# sensorHubRev6.net
KiCad netlist of a schematic drawn in EAGLE
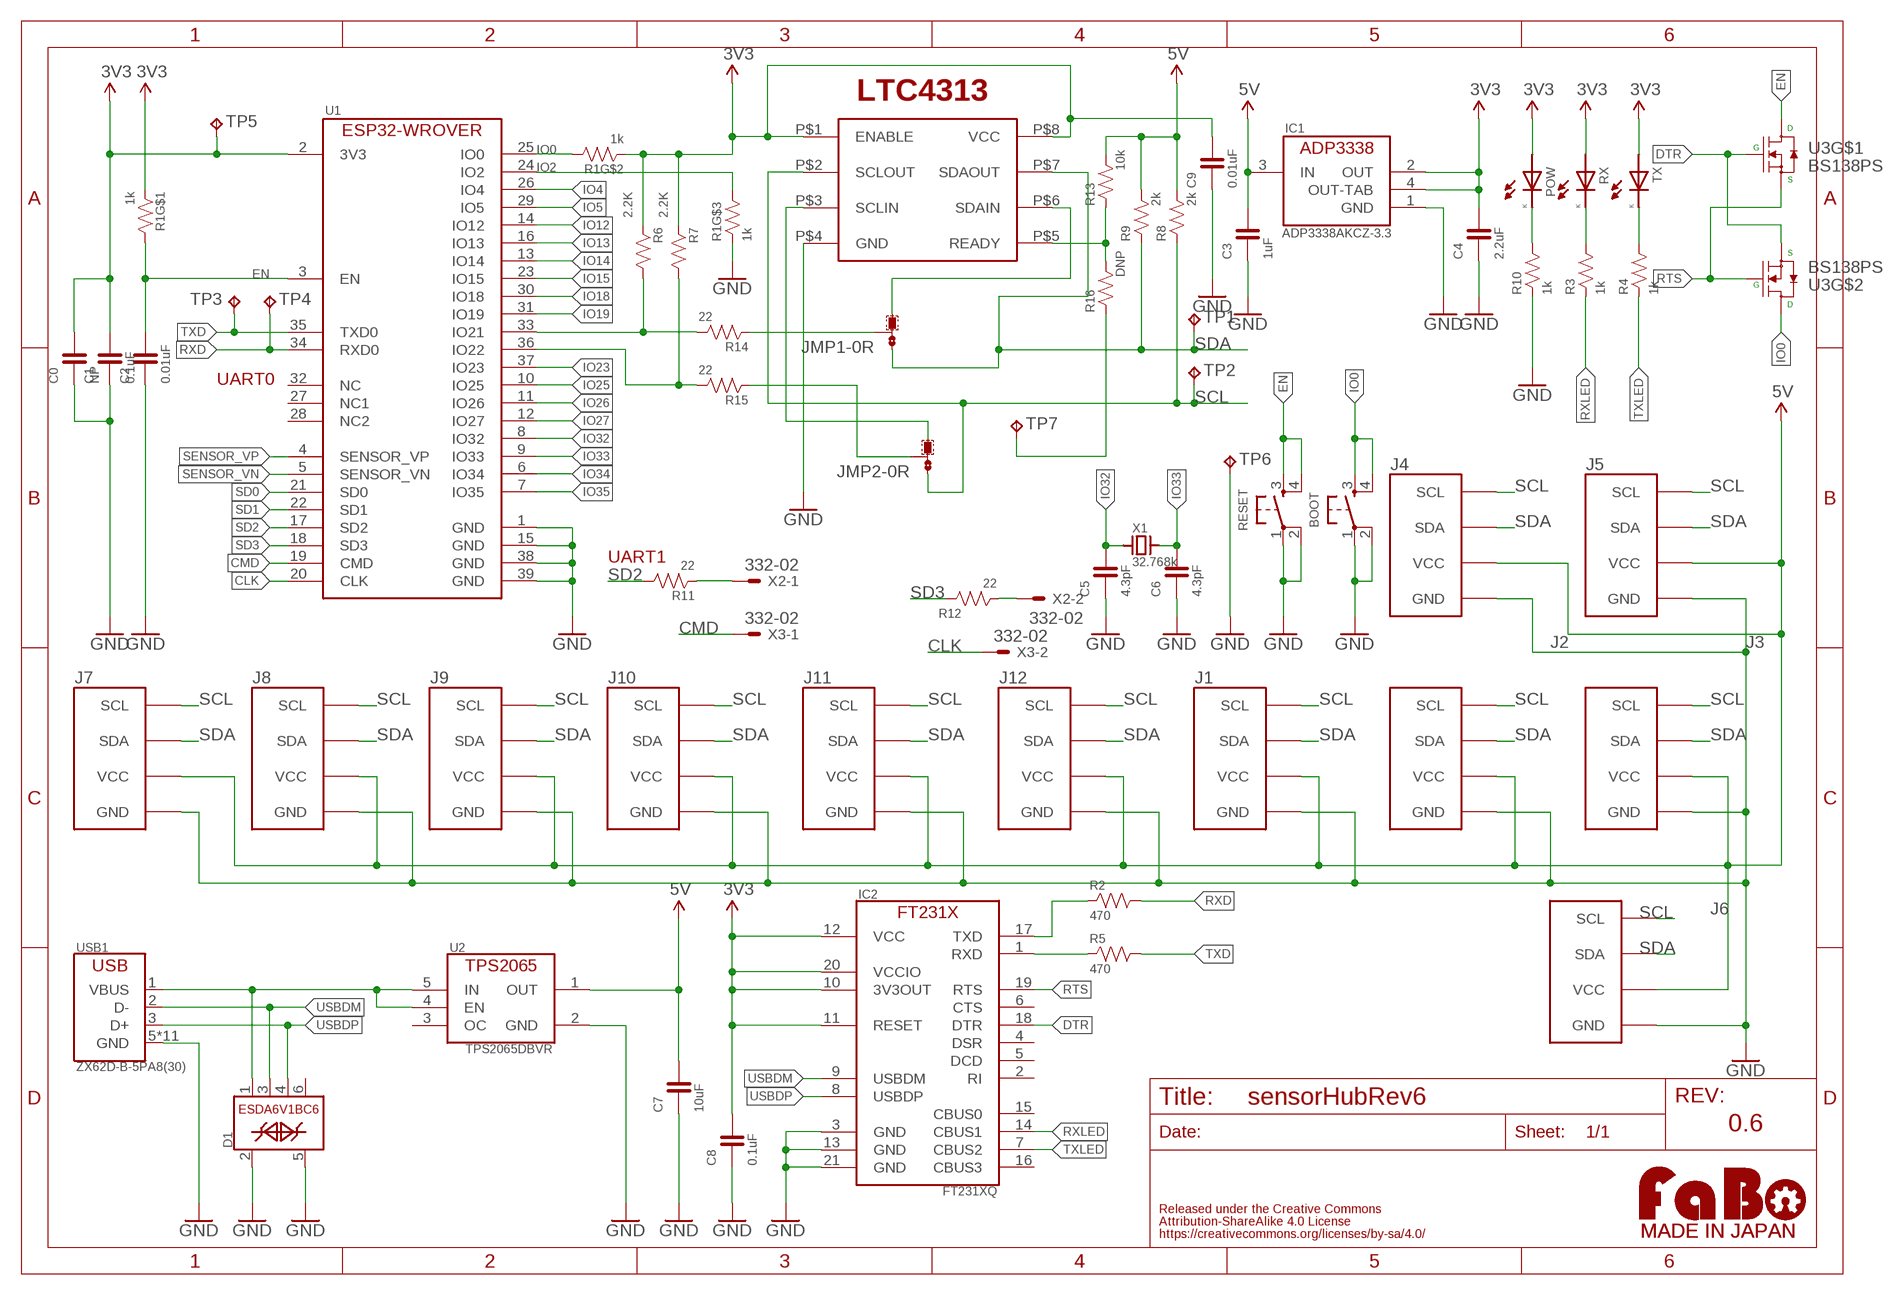
[diagram p0: schematic, sheet 1]

(export (version "E")
  (design (tool "Eeschema 10.0.6"))
  (components
    (comp (ref "BOOT")
      (value "TACTILE-KMR2")
      (footprint "eagle-import:KMR2-TACT")
      (libsource (lib "eagle-import") (part "TACTILE-KMR2"))
    )
    (comp (ref "C0")
      (value "NP")
      (footprint "eagle-import:MULTIPAD0603")
      (libsource (lib "eagle-import") (part "CAPACITOR-M"))
    )
    (comp (ref "C1")
      (value "0.1uF")
      (footprint "eagle-import:EIA0603")
      (libsource (lib "eagle-import") (part "CAPACITOR-0603"))
    )
    (comp (ref "C2")
      (value "0.01uF")
      (footprint "eagle-import:EIA0603")
      (libsource (lib "eagle-import") (part "CAPACITOR-0603"))
    )
    (comp (ref "C3")
      (value "1uF")
      (footprint "eagle-import:EIA0603")
      (libsource (lib "eagle-import") (part "CAPACITOR-0603"))
    )
    (comp (ref "C4")
      (value "2.2uF")
      (footprint "eagle-import:EIA0603")
      (libsource (lib "eagle-import") (part "CAPACITOR-0603"))
    )
    (comp (ref "C5")
      (value "4.3pF")
      (footprint "eagle-import:EIA0603")
      (libsource (lib "eagle-import") (part "CAPACITOR-0603"))
    )
    (comp (ref "C6")
      (value "4.3pF")
      (footprint "eagle-import:EIA0603")
      (libsource (lib "eagle-import") (part "CAPACITOR-0603"))
    )
    (comp (ref "C7")
      (value "10uF")
      (footprint "eagle-import:EIA0603")
      (libsource (lib "eagle-import") (part "CAPACITOR-0603"))
    )
    (comp (ref "C8")
      (value "0.1uF")
      (footprint "eagle-import:EIA0603")
      (libsource (lib "eagle-import") (part "CAPACITOR-0603"))
    )
    (comp (ref "C9")
      (value "0.01uF")
      (footprint "eagle-import:EIA0603")
      (libsource (lib "eagle-import") (part "CAPACITOR-0603"))
    )
    (comp (ref "D1")
      (value "ESDA6V1BC6")
      (footprint "eagle-import:SOT-23-6L")
      (libsource (lib "eagle-import") (part "ESDA6V1BC6"))
    )
    (comp (ref "IC1")
      (value "ADP3338AKCZ-3.3")
      (footprint "eagle-import:SOT-223-KC3")
      (libsource (lib "eagle-import") (part "ADP3338AKCZ"))
    )
    (comp (ref "IC2")
      (value "FT231XQ")
      (footprint "eagle-import:QFN-20")
      (libsource (lib "eagle-import") (part "FT231XQ"))
    )
    (comp (ref "J1")
      (value "FABO_BRICK_I2C-S04B-PASK-2")
      (footprint "eagle-import:FABO_BRICK_I2C_S04B-PASK-2")
      (libsource (lib "eagle-import") (part "FABO_BRICK_I2C-S04B-PASK-2"))
    )
    (comp (ref "J2")
      (value "FABO_BRICK_I2C-S04B-PASK-2")
      (footprint "eagle-import:FABO_BRICK_I2C_S04B-PASK-2")
      (libsource (lib "eagle-import") (part "FABO_BRICK_I2C-S04B-PASK-2"))
    )
    (comp (ref "J3")
      (value "FABO_BRICK_I2C-S04B-PASK-2")
      (footprint "eagle-import:FABO_BRICK_I2C_S04B-PASK-2")
      (libsource (lib "eagle-import") (part "FABO_BRICK_I2C-S04B-PASK-2"))
    )
    (comp (ref "J4")
      (value "FABO_BRICK_I2C-S04B-PASK-2")
      (footprint "eagle-import:FABO_BRICK_I2C_S04B-PASK-2")
      (libsource (lib "eagle-import") (part "FABO_BRICK_I2C-S04B-PASK-2"))
    )
    (comp (ref "J5")
      (value "FABO_BRICK_I2C-S04B-PASK-2")
      (footprint "eagle-import:FABO_BRICK_I2C_S04B-PASK-2")
      (libsource (lib "eagle-import") (part "FABO_BRICK_I2C-S04B-PASK-2"))
    )
    (comp (ref "J6")
      (value "FABO_BRICK_I2C-S04B-PASK-2")
      (footprint "eagle-import:FABO_BRICK_I2C_S04B-PASK-2")
      (libsource (lib "eagle-import") (part "FABO_BRICK_I2C-S04B-PASK-2"))
    )
    (comp (ref "J7")
      (value "FABO_BRICK_I2C-S04B-PASK-2")
      (footprint "eagle-import:FABO_BRICK_I2C_S04B-PASK-2")
      (libsource (lib "eagle-import") (part "FABO_BRICK_I2C-S04B-PASK-2"))
    )
    (comp (ref "J8")
      (value "FABO_BRICK_I2C-S04B-PASK-2")
      (footprint "eagle-import:FABO_BRICK_I2C_S04B-PASK-2")
      (libsource (lib "eagle-import") (part "FABO_BRICK_I2C-S04B-PASK-2"))
    )
    (comp (ref "J9")
      (value "FABO_BRICK_I2C-S04B-PASK-2")
      (footprint "eagle-import:FABO_BRICK_I2C_S04B-PASK-2")
      (libsource (lib "eagle-import") (part "FABO_BRICK_I2C-S04B-PASK-2"))
    )
    (comp (ref "J10")
      (value "FABO_BRICK_I2C-S04B-PASK-2")
      (footprint "eagle-import:FABO_BRICK_I2C_S04B-PASK-2")
      (libsource (lib "eagle-import") (part "FABO_BRICK_I2C-S04B-PASK-2"))
    )
    (comp (ref "J11")
      (value "FABO_BRICK_I2C-S04B-PASK-2")
      (footprint "eagle-import:FABO_BRICK_I2C_S04B-PASK-2")
      (libsource (lib "eagle-import") (part "FABO_BRICK_I2C-S04B-PASK-2"))
    )
    (comp (ref "J12")
      (value "FABO_BRICK_I2C-S04B-PASK-2")
      (footprint "eagle-import:FABO_BRICK_I2C_S04B-PASK-2")
      (libsource (lib "eagle-import") (part "FABO_BRICK_I2C-S04B-PASK-2"))
    )
    (comp (ref "JMP1")
      (value "0R-JUMPA")
      (footprint "eagle-import:A0R-JMP")
      (libsource (lib "eagle-import") (part "0R-JUMPA"))
    )
    (comp (ref "JMP2")
      (value "0R-JUMPA")
      (footprint "eagle-import:A0R-JMP")
      (libsource (lib "eagle-import") (part "0R-JUMPA"))
    )
    (comp (ref "LOGO1")
      (value "LOGO_FABO-M_BOTTOM")
      (footprint "eagle-import:LOGO_FABO_M_BOTTOM")
      (libsource (lib "eagle-import") (part "LOGO_FABO-M_BOTTOM"))
    )
    (comp (ref "POW")
      (value "LED-0603")
      (footprint "eagle-import:LED_0603")
      (libsource (lib "eagle-import") (part "LED-0603"))
    )
    (comp (ref "R1")
      (value "1k")
      (footprint "eagle-import:EXBV8V")
      (libsource (lib "eagle-import") (part "RESISTOR_ARRAY"))
    )
    (comp (ref "R2")
      (value "470")
      (footprint "eagle-import:EIA0603")
      (libsource (lib "eagle-import") (part "RESISTOR-0603"))
    )
    (comp (ref "R3")
      (value "1k")
      (footprint "eagle-import:EIA0603")
      (libsource (lib "eagle-import") (part "RESISTOR-0603"))
    )
    (comp (ref "R4")
      (value "1k")
      (footprint "eagle-import:EIA0603")
      (libsource (lib "eagle-import") (part "RESISTOR-0603"))
    )
    (comp (ref "R5")
      (value "470")
      (footprint "eagle-import:EIA0603")
      (libsource (lib "eagle-import") (part "RESISTOR-0603"))
    )
    (comp (ref "R6")
      (value "2.2K")
      (footprint "eagle-import:EIA0603")
      (libsource (lib "eagle-import") (part "RESISTOR-0603"))
    )
    (comp (ref "R7")
      (value "2.2K")
      (footprint "eagle-import:EIA0603")
      (libsource (lib "eagle-import") (part "RESISTOR-0603"))
    )
    (comp (ref "R8")
      (value "2k")
      (footprint "eagle-import:EIA0603")
      (libsource (lib "eagle-import") (part "RESISTOR-0603"))
    )
    (comp (ref "R9")
      (value "2k")
      (footprint "eagle-import:EIA0603")
      (libsource (lib "eagle-import") (part "RESISTOR-0603"))
    )
    (comp (ref "R10")
      (value "1k")
      (footprint "eagle-import:EIA0603")
      (libsource (lib "eagle-import") (part "RESISTOR-0603"))
    )
    (comp (ref "R11")
      (value "22")
      (footprint "eagle-import:EIA0603")
      (libsource (lib "eagle-import") (part "RESISTOR-0603"))
    )
    (comp (ref "R12")
      (value "22")
      (footprint "eagle-import:EIA0603")
      (libsource (lib "eagle-import") (part "RESISTOR-0603"))
    )
    (comp (ref "R13")
      (value "10k")
      (footprint "eagle-import:EIA0603")
      (libsource (lib "eagle-import") (part "RESISTOR-0603"))
    )
    (comp (ref "R14")
      (value "22")
      (footprint "eagle-import:EIA0603")
      (libsource (lib "eagle-import") (part "RESISTOR-0603"))
    )
    (comp (ref "R15")
      (value "22")
      (footprint "eagle-import:EIA0603")
      (libsource (lib "eagle-import") (part "RESISTOR-0603"))
    )
    (comp (ref "R16")
      (value "DNP")
      (footprint "eagle-import:EIA0603")
      (libsource (lib "eagle-import") (part "RESISTOR-0603"))
    )
    (comp (ref "RESET")
      (value "TACTILE-KMR2")
      (footprint "eagle-import:KMR2-TACT")
      (libsource (lib "eagle-import") (part "TACTILE-KMR2"))
    )
    (comp (ref "RX")
      (value "LED-0603")
      (footprint "eagle-import:LED_0603")
      (libsource (lib "eagle-import") (part "LED-0603"))
    )
    (comp (ref "TP1")
      (value "TPB1,27")
      (footprint "eagle-import:B1,27")
      (libsource (lib "eagle-import") (part "TPB1,27"))
    )
    (comp (ref "TP2")
      (value "TPB1,27")
      (footprint "eagle-import:B1,27")
      (libsource (lib "eagle-import") (part "TPB1,27"))
    )
    (comp (ref "TP3")
      (value "TPB1,27")
      (footprint "eagle-import:B1,27")
      (libsource (lib "eagle-import") (part "TPB1,27"))
    )
    (comp (ref "TP4")
      (value "TPB1,27")
      (footprint "eagle-import:B1,27")
      (libsource (lib "eagle-import") (part "TPB1,27"))
    )
    (comp (ref "TP5")
      (value "TPB1,27")
      (footprint "eagle-import:B1,27")
      (libsource (lib "eagle-import") (part "TPB1,27"))
    )
    (comp (ref "TP6")
      (value "TPB1,27")
      (footprint "eagle-import:B1,27")
      (libsource (lib "eagle-import") (part "TPB1,27"))
    )
    (comp (ref "TP7")
      (value "TPB1,27")
      (footprint "eagle-import:B1,27")
      (libsource (lib "eagle-import") (part "TPB1,27"))
    )
    (comp (ref "TX")
      (value "LED-0603")
      (footprint "eagle-import:LED_0603")
      (libsource (lib "eagle-import") (part "LED-0603"))
    )
    (comp (ref "U1")
      (value "ESP32-WROVER-B")
      (footprint "eagle-import:ESP32-WROVER-B")
      (libsource (lib "eagle-import") (part "ESP32-WROVER-B"))
    )
    (comp (ref "U2")
      (value "TPS2065DBVR")
      (footprint "eagle-import:SOT-23-5")
      (libsource (lib "eagle-import") (part "TPS2065DBV"))
    )
    (comp (ref "U3")
      (value "BS138PS")
      (footprint "eagle-import:SOT-363")
      (libsource (lib "eagle-import") (part "BS138PS"))
    )
    (comp (ref "U5")
      (value "LTC4313")
      (footprint "eagle-import:LTC4313")
      (libsource (lib "eagle-import") (part "LTC4313"))
    )
    (comp (ref "USB1")
      (value "ZX62D-B-5PA8(30)")
      (footprint "eagle-import:ZX62D-B-5PA8")
      (libsource (lib "eagle-import") (part "USB-ZX62D"))
    )
    (comp (ref "X1")
      (value "32.768k")
      (footprint "eagle-import:ABS07")
      (libsource (lib "eagle-import") (part "CRYSTAL-ABS07"))
    )
    (comp (ref "X2")
      (value "332-02")
      (footprint "eagle-import:332-02")
      (libsource (lib "eagle-import") (part "332-02"))
    )
    (comp (ref "X3")
      (value "332-02")
      (footprint "eagle-import:332-02")
      (libsource (lib "eagle-import") (part "332-02"))
    )
  )
  (nets
    (net (code "1") (name "/IO2") (class "Default")
      (node (ref "R1") (pin "6") (pinfunction "2_6") (pintype "bidirectional"))
      (node (ref "U1") (pin "24") (pinfunction "IO2_24") (pintype "bidirectional"))
    )
    (net (code "2") (name "/SCL") (class "Default")
      (node (ref "J1") (pin "SCL") (pinfunction "SCL_SCL") (pintype "bidirectional"))
      (node (ref "J10") (pin "SCL") (pinfunction "SCL_SCL") (pintype "bidirectional"))
      (node (ref "J11") (pin "SCL") (pinfunction "SCL_SCL") (pintype "bidirectional"))
      (node (ref "J12") (pin "SCL") (pinfunction "SCL_SCL") (pintype "bidirectional"))
      (node (ref "J2") (pin "SCL") (pinfunction "SCL_SCL") (pintype "bidirectional"))
      (node (ref "J3") (pin "SCL") (pinfunction "SCL_SCL") (pintype "bidirectional"))
      (node (ref "J4") (pin "SCL") (pinfunction "SCL_SCL") (pintype "bidirectional"))
      (node (ref "J5") (pin "SCL") (pinfunction "SCL_SCL") (pintype "bidirectional"))
      (node (ref "J6") (pin "SCL") (pinfunction "SCL_SCL") (pintype "bidirectional"))
      (node (ref "J7") (pin "SCL") (pinfunction "SCL_SCL") (pintype "bidirectional"))
      (node (ref "J8") (pin "SCL") (pinfunction "SCL_SCL") (pintype "bidirectional"))
      (node (ref "J9") (pin "SCL") (pinfunction "SCL_SCL") (pintype "bidirectional"))
      (node (ref "JMP2") (pin "1") (pinfunction "1_1") (pintype "passive"))
      (node (ref "R8") (pin "1") (pinfunction "1_1") (pintype "bidirectional"))
      (node (ref "TP2") (pin "TP") (pinfunction "TP_TP") (pintype "input"))
      (node (ref "U5") (pin "P$2") (pinfunction "SCLOUT_P$2") (pintype "bidirectional"))
    )
    (net (code "3") (name "/SDA") (class "Default")
      (node (ref "J1") (pin "SDA") (pinfunction "SDA_SDA") (pintype "bidirectional"))
      (node (ref "J10") (pin "SDA") (pinfunction "SDA_SDA") (pintype "bidirectional"))
      (node (ref "J11") (pin "SDA") (pinfunction "SDA_SDA") (pintype "bidirectional"))
      (node (ref "J12") (pin "SDA") (pinfunction "SDA_SDA") (pintype "bidirectional"))
      (node (ref "J2") (pin "SDA") (pinfunction "SDA_SDA") (pintype "bidirectional"))
      (node (ref "J3") (pin "SDA") (pinfunction "SDA_SDA") (pintype "bidirectional"))
      (node (ref "J4") (pin "SDA") (pinfunction "SDA_SDA") (pintype "bidirectional"))
      (node (ref "J5") (pin "SDA") (pinfunction "SDA_SDA") (pintype "bidirectional"))
      (node (ref "J6") (pin "SDA") (pinfunction "SDA_SDA") (pintype "bidirectional"))
      (node (ref "J7") (pin "SDA") (pinfunction "SDA_SDA") (pintype "bidirectional"))
      (node (ref "J8") (pin "SDA") (pinfunction "SDA_SDA") (pintype "bidirectional"))
      (node (ref "J9") (pin "SDA") (pinfunction "SDA_SDA") (pintype "bidirectional"))
      (node (ref "JMP1") (pin "1") (pinfunction "1_1") (pintype "passive"))
      (node (ref "R9") (pin "1") (pinfunction "1_1") (pintype "bidirectional"))
      (node (ref "TP1") (pin "TP") (pinfunction "TP_TP") (pintype "input"))
      (node (ref "U5") (pin "P$7") (pinfunction "SDAOUT_P$7") (pintype "bidirectional"))
    )
    (net (code "4") (name "3V3") (class "Default")
      (node (ref "C0") (pin "2") (pinfunction "2_2") (pintype "passive"))
      (node (ref "C1") (pin "2") (pinfunction "2_2") (pintype "passive"))
      (node (ref "C4") (pin "2") (pinfunction "2_2") (pintype "passive"))
      (node (ref "C8") (pin "2") (pinfunction "2_2") (pintype "passive"))
      (node (ref "C9") (pin "2") (pinfunction "2_2") (pintype "passive"))
      (node (ref "IC1") (pin "2") (pinfunction "OUT_2") (pintype "bidirectional"))
      (node (ref "IC1") (pin "4") (pinfunction "OUT-TAB_4") (pintype "bidirectional"))
      (node (ref "IC2") (pin "10") (pinfunction "3V3OUT_10") (pintype "bidirectional"))
      (node (ref "IC2") (pin "11") (pinfunction "RESET_11") (pintype "bidirectional"))
      (node (ref "IC2") (pin "12") (pinfunction "VCC_12") (pintype "bidirectional"))
      (node (ref "IC2") (pin "20") (pinfunction "VCCIO_20") (pintype "bidirectional"))
      (node (ref "POW") (pin "A") (pinfunction "ANODE_A") (pintype "passive"))
      (node (ref "R1") (pin "1") (pinfunction "1_1") (pintype "bidirectional"))
      (node (ref "R1") (pin "2") (pinfunction "1_2") (pintype "bidirectional"))
      (node (ref "R6") (pin "1") (pinfunction "1_1") (pintype "bidirectional"))
      (node (ref "R7") (pin "1") (pinfunction "1_1") (pintype "bidirectional"))
      (node (ref "RX") (pin "A") (pinfunction "ANODE_A") (pintype "passive"))
      (node (ref "TP5") (pin "TP") (pinfunction "TP_TP") (pintype "input"))
      (node (ref "TX") (pin "A") (pinfunction "ANODE_A") (pintype "passive"))
      (node (ref "U1") (pin "2") (pinfunction "3V3_2") (pintype "bidirectional"))
      (node (ref "U5") (pin "P$1") (pinfunction "ENABLE_P$1") (pintype "bidirectional"))
      (node (ref "U5") (pin "P$8") (pinfunction "VCC_P$8") (pintype "bidirectional"))
    )
    (net (code "5") (name "5V") (class "Default")
      (node (ref "C3") (pin "2") (pinfunction "2_2") (pintype "passive"))
      (node (ref "C7") (pin "2") (pinfunction "2_2") (pintype "passive"))
      (node (ref "IC1") (pin "3") (pinfunction "IN_3") (pintype "bidirectional"))
      (node (ref "J1") (pin "VCC") (pinfunction "VCC_VCC") (pintype "bidirectional"))
      (node (ref "J10") (pin "VCC") (pinfunction "VCC_VCC") (pintype "bidirectional"))
      (node (ref "J11") (pin "VCC") (pinfunction "VCC_VCC") (pintype "bidirectional"))
      (node (ref "J12") (pin "VCC") (pinfunction "VCC_VCC") (pintype "bidirectional"))
      (node (ref "J2") (pin "VCC") (pinfunction "VCC_VCC") (pintype "bidirectional"))
      (node (ref "J3") (pin "VCC") (pinfunction "VCC_VCC") (pintype "bidirectional"))
      (node (ref "J4") (pin "VCC") (pinfunction "VCC_VCC") (pintype "bidirectional"))
      (node (ref "J5") (pin "VCC") (pinfunction "VCC_VCC") (pintype "bidirectional"))
      (node (ref "J6") (pin "VCC") (pinfunction "VCC_VCC") (pintype "bidirectional"))
      (node (ref "J7") (pin "VCC") (pinfunction "VCC_VCC") (pintype "bidirectional"))
      (node (ref "J8") (pin "VCC") (pinfunction "VCC_VCC") (pintype "bidirectional"))
      (node (ref "J9") (pin "VCC") (pinfunction "VCC_VCC") (pintype "bidirectional"))
      (node (ref "R13") (pin "2") (pinfunction "2_2") (pintype "bidirectional"))
      (node (ref "R8") (pin "2") (pinfunction "2_2") (pintype "bidirectional"))
      (node (ref "R9") (pin "2") (pinfunction "2_2") (pintype "bidirectional"))
      (node (ref "U2") (pin "1") (pinfunction "OUT_1") (pintype "bidirectional"))
    )
    (net (code "6") (name "CLK") (class "Default")
      (node (ref "U1") (pin "20") (pinfunction "CLK_20") (pintype "bidirectional"))
      (node (ref "X3") (pin "2") (pinfunction "S_2") (pintype "passive"))
    )
    (net (code "7") (name "CMD") (class "Default")
      (node (ref "U1") (pin "19") (pinfunction "CMD_19") (pintype "bidirectional"))
      (node (ref "X3") (pin "1") (pinfunction "S_1") (pintype "passive"))
    )
    (net (code "8") (name "DTR") (class "Default")
      (node (ref "IC2") (pin "18") (pinfunction "DTR_18") (pintype "bidirectional"))
      (node (ref "U3") (pin "2") (pinfunction "G_2") (pintype "passive"))
      (node (ref "U3") (pin "4") (pinfunction "S_4") (pintype "passive"))
    )
    (net (code "9") (name "EN") (class "Default")
      (node (ref "C2") (pin "2") (pinfunction "2_2") (pintype "passive"))
      (node (ref "R1") (pin "8") (pinfunction "2_8") (pintype "bidirectional"))
      (node (ref "RESET") (pin "3") (pinfunction "3_3") (pintype "passive"))
      (node (ref "RESET") (pin "4") (pinfunction "4_4") (pintype "passive"))
      (node (ref "U1") (pin "3") (pinfunction "EN_3") (pintype "bidirectional"))
      (node (ref "U3") (pin "6") (pinfunction "D_6") (pintype "passive"))
    )
    (net (code "10") (name "GND") (class "Default")
      (node (ref "BOOT") (pin "1") (pinfunction "1_1") (pintype "passive"))
      (node (ref "BOOT") (pin "2") (pinfunction "2_2") (pintype "passive"))
      (node (ref "C0") (pin "1") (pinfunction "1_1") (pintype "passive"))
      (node (ref "C1") (pin "1") (pinfunction "1_1") (pintype "passive"))
      (node (ref "C2") (pin "1") (pinfunction "1_1") (pintype "passive"))
      (node (ref "C3") (pin "1") (pinfunction "1_1") (pintype "passive"))
      (node (ref "C4") (pin "1") (pinfunction "1_1") (pintype "passive"))
      (node (ref "C5") (pin "1") (pinfunction "1_1") (pintype "passive"))
      (node (ref "C6") (pin "1") (pinfunction "1_1") (pintype "passive"))
      (node (ref "C7") (pin "1") (pinfunction "1_1") (pintype "passive"))
      (node (ref "C8") (pin "1") (pinfunction "1_1") (pintype "passive"))
      (node (ref "C9") (pin "1") (pinfunction "1_1") (pintype "passive"))
      (node (ref "D1") (pin "2") (pinfunction "2_2") (pintype "bidirectional"))
      (node (ref "D1") (pin "5") (pinfunction "5_5") (pintype "bidirectional"))
      (node (ref "IC1") (pin "1") (pinfunction "GND_1") (pintype "bidirectional"))
      (node (ref "IC2") (pin "13") (pinfunction "GND_13") (pintype "bidirectional"))
      (node (ref "IC2") (pin "21") (pinfunction "GND_21") (pintype "bidirectional"))
      (node (ref "IC2") (pin "3") (pinfunction "GND_3") (pintype "bidirectional"))
      (node (ref "J1") (pin "GND") (pinfunction "GND_GND") (pintype "bidirectional"))
      (node (ref "J10") (pin "GND") (pinfunction "GND_GND") (pintype "bidirectional"))
      (node (ref "J11") (pin "GND") (pinfunction "GND_GND") (pintype "bidirectional"))
      (node (ref "J12") (pin "GND") (pinfunction "GND_GND") (pintype "bidirectional"))
      (node (ref "J2") (pin "GND") (pinfunction "GND_GND") (pintype "bidirectional"))
      (node (ref "J3") (pin "GND") (pinfunction "GND_GND") (pintype "bidirectional"))
      (node (ref "J4") (pin "GND") (pinfunction "GND_GND") (pintype "bidirectional"))
      (node (ref "J5") (pin "GND") (pinfunction "GND_GND") (pintype "bidirectional"))
      (node (ref "J6") (pin "GND") (pinfunction "GND_GND") (pintype "bidirectional"))
      (node (ref "J7") (pin "GND") (pinfunction "GND_GND") (pintype "bidirectional"))
      (node (ref "J8") (pin "GND") (pinfunction "GND_GND") (pintype "bidirectional"))
      (node (ref "J9") (pin "GND") (pinfunction "GND_GND") (pintype "bidirectional"))
      (node (ref "R1") (pin "3") (pinfunction "1_3") (pintype "bidirectional"))
      (node (ref "R10") (pin "1") (pinfunction "1_1") (pintype "bidirectional"))
      (node (ref "RESET") (pin "1") (pinfunction "1_1") (pintype "passive"))
      (node (ref "RESET") (pin "2") (pinfunction "2_2") (pintype "passive"))
      (node (ref "TP6") (pin "TP") (pinfunction "TP_TP") (pintype "input"))
      (node (ref "U1") (pin "1") (pinfunction "GND_1") (pintype "bidirectional"))
      (node (ref "U1") (pin "15") (pinfunction "GND_15") (pintype "bidirectional"))
      (node (ref "U1") (pin "38") (pinfunction "GND_38") (pintype "bidirectional"))
      (node (ref "U1") (pin "39") (pinfunction "GND_39") (pintype "bidirectional"))
      (node (ref "U2") (pin "2") (pinfunction "GND_2") (pintype "bidirectional"))
      (node (ref "U5") (pin "P$4") (pinfunction "GND_P$4") (pintype "bidirectional"))
      (node (ref "USB1") (pin "5") (pinfunction "GND_5") (pintype "bidirectional"))
      (node (ref "USB1") (pin "B1") (pinfunction "GND_B1") (pintype "bidirectional"))
      (node (ref "USB1") (pin "B2") (pinfunction "GND_B2") (pintype "bidirectional"))
      (node (ref "USB1") (pin "B3") (pinfunction "GND_B3") (pintype "bidirectional"))
      (node (ref "USB1") (pin "B4") (pinfunction "GND_B4") (pintype "bidirectional"))
      (node (ref "USB1") (pin "T1") (pinfunction "GND_T1") (pintype "bidirectional"))
      (node (ref "USB1") (pin "T2") (pinfunction "GND_T2") (pintype "bidirectional"))
      (node (ref "USB1") (pin "T3") (pinfunction "GND_T3") (pintype "bidirectional"))
      (node (ref "USB1") (pin "T4") (pinfunction "GND_T4") (pintype "bidirectional"))
      (node (ref "USB1") (pin "T5") (pinfunction "GND_T5") (pintype "bidirectional"))
      (node (ref "USB1") (pin "T6") (pinfunction "GND_T6") (pintype "bidirectional"))
    )
    (net (code "11") (name "IO0") (class "Default")
      (node (ref "BOOT") (pin "3") (pinfunction "3_3") (pintype "passive"))
      (node (ref "BOOT") (pin "4") (pinfunction "4_4") (pintype "passive"))
      (node (ref "R1") (pin "7") (pinfunction "2_7") (pintype "bidirectional"))
      (node (ref "U1") (pin "25") (pinfunction "IO0_25") (pintype "bidirectional"))
      (node (ref "U3") (pin "3") (pinfunction "D_3") (pintype "passive"))
    )
    (net (code "12") (name "IO4") (class "Default")
      (node (ref "U1") (pin "26") (pinfunction "IO4_26") (pintype "bidirectional"))
    )
    (net (code "13") (name "IO5") (class "Default")
      (node (ref "U1") (pin "29") (pinfunction "IO5_29") (pintype "bidirectional"))
    )
    (net (code "14") (name "IO12") (class "Default")
      (node (ref "U1") (pin "14") (pinfunction "IO12_14") (pintype "bidirectional"))
    )
    (net (code "15") (name "IO13") (class "Default")
      (node (ref "U1") (pin "16") (pinfunction "IO13_16") (pintype "bidirectional"))
    )
    (net (code "16") (name "IO14") (class "Default")
      (node (ref "U1") (pin "13") (pinfunction "IO14_13") (pintype "bidirectional"))
    )
    (net (code "17") (name "IO15") (class "Default")
      (node (ref "U1") (pin "23") (pinfunction "IO15_23") (pintype "bidirectional"))
    )
    (net (code "18") (name "IO18") (class "Default")
      (node (ref "U1") (pin "30") (pinfunction "IO18_30") (pintype "bidirectional"))
    )
    (net (code "19") (name "IO19") (class "Default")
      (node (ref "U1") (pin "31") (pinfunction "IO19_31") (pintype "bidirectional"))
    )
    (net (code "20") (name "IO23") (class "Default")
      (node (ref "U1") (pin "37") (pinfunction "IO23_37") (pintype "bidirectional"))
    )
    (net (code "21") (name "IO25") (class "Default")
      (node (ref "U1") (pin "10") (pinfunction "IO25_10") (pintype "bidirectional"))
    )
    (net (code "22") (name "IO26") (class "Default")
      (node (ref "U1") (pin "11") (pinfunction "IO26_11") (pintype "bidirectional"))
    )
    (net (code "23") (name "IO27") (class "Default")
      (node (ref "U1") (pin "12") (pinfunction "IO27_12") (pintype "bidirectional"))
    )
    (net (code "24") (name "IO32") (class "Default")
      (node (ref "C5") (pin "2") (pinfunction "2_2") (pintype "passive"))
      (node (ref "U1") (pin "8") (pinfunction "IO32_8") (pintype "bidirectional"))
      (node (ref "X1") (pin "1") (pinfunction "P$1_1") (pintype "bidirectional"))
    )
    (net (code "25") (name "IO33") (class "Default")
      (node (ref "C6") (pin "2") (pinfunction "2_2") (pintype "passive"))
      (node (ref "U1") (pin "9") (pinfunction "IO33_9") (pintype "bidirectional"))
      (node (ref "X1") (pin "2") (pinfunction "P$2_2") (pintype "bidirectional"))
    )
    (net (code "26") (name "IO34") (class "Default")
      (node (ref "U1") (pin "6") (pinfunction "IO34_6") (pintype "bidirectional"))
    )
    (net (code "27") (name "IO35") (class "Default")
      (node (ref "U1") (pin "7") (pinfunction "IO35_7") (pintype "bidirectional"))
    )
    (net (code "28") (name "Net-(IC2-RXD)") (class "Default")
      (node (ref "IC2") (pin "1") (pinfunction "RXD_1") (pintype "bidirectional"))
      (node (ref "R5") (pin "1") (pinfunction "1_1") (pintype "bidirectional"))
    )
    (net (code "29") (name "Net-(IC2-TXD)") (class "Default")
      (node (ref "IC2") (pin "17") (pinfunction "TXD_17") (pintype "bidirectional"))
      (node (ref "R2") (pin "1") (pinfunction "1_1") (pintype "bidirectional"))
    )
    (net (code "30") (name "Net-(JMP1-Pad2)") (class "Default")
      (node (ref "JMP1") (pin "2") (pinfunction "2_2") (pintype "passive"))
      (node (ref "R14") (pin "1") (pinfunction "1_1") (pintype "bidirectional"))
    )
    (net (code "31") (name "Net-(JMP2-Pad2)") (class "Default")
      (node (ref "JMP2") (pin "2") (pinfunction "2_2") (pintype "passive"))
      (node (ref "R15") (pin "1") (pinfunction "1_1") (pintype "bidirectional"))
    )
    (net (code "32") (name "Net-(POW-CATHODE)") (class "Default")
      (node (ref "POW") (pin "K") (pinfunction "CATHODE_K") (pintype "passive"))
      (node (ref "R10") (pin "2") (pinfunction "2_2") (pintype "bidirectional"))
    )
    (net (code "33") (name "Net-(R16-Pad1)") (class "Default")
      (node (ref "R16") (pin "1") (pinfunction "1_1") (pintype "bidirectional"))
      (node (ref "TP7") (pin "TP") (pinfunction "TP_TP") (pintype "input"))
    )
    (net (code "34") (name "Net-(RX-CATHODE)") (class "Default")
      (node (ref "R3") (pin "2") (pinfunction "2_2") (pintype "bidirectional"))
      (node (ref "RX") (pin "K") (pinfunction "CATHODE_K") (pintype "passive"))
    )
    (net (code "35") (name "Net-(TX-CATHODE)") (class "Default")
      (node (ref "R4") (pin "2") (pinfunction "2_2") (pintype "bidirectional"))
      (node (ref "TX") (pin "K") (pinfunction "CATHODE_K") (pintype "passive"))
    )
    (net (code "36") (name "Net-(U1-IO21)") (class "Default")
      (node (ref "R14") (pin "2") (pinfunction "2_2") (pintype "bidirectional"))
      (node (ref "R6") (pin "2") (pinfunction "2_2") (pintype "bidirectional"))
      (node (ref "U1") (pin "33") (pinfunction "IO21_33") (pintype "bidirectional"))
    )
    (net (code "37") (name "Net-(U1-IO22)") (class "Default")
      (node (ref "R15") (pin "2") (pinfunction "2_2") (pintype "bidirectional"))
      (node (ref "R7") (pin "2") (pinfunction "2_2") (pintype "bidirectional"))
      (node (ref "U1") (pin "36") (pinfunction "IO22_36") (pintype "bidirectional"))
    )
    (net (code "38") (name "Net-(U2-EN)") (class "Default")
      (node (ref "D1") (pin "1") (pinfunction "1_1") (pintype "bidirectional"))
      (node (ref "U2") (pin "4") (pinfunction "EN_4") (pintype "bidirectional"))
      (node (ref "U2") (pin "5") (pinfunction "IN_5") (pintype "bidirectional"))
      (node (ref "USB1") (pin "1") (pinfunction "VBUS_1") (pintype "bidirectional"))
    )
    (net (code "39") (name "Net-(U5-READY)") (class "Default")
      (node (ref "R13") (pin "1") (pinfunction "1_1") (pintype "bidirectional"))
      (node (ref "R16") (pin "2") (pinfunction "2_2") (pintype "bidirectional"))
      (node (ref "U5") (pin "P$5") (pinfunction "READY_P$5") (pintype "bidirectional"))
    )
    (net (code "40") (name "Net-(U5-SCLIN)") (class "Default")
      (node (ref "JMP2") (pin "3") (pinfunction "3_3") (pintype "passive"))
      (node (ref "U5") (pin "P$3") (pinfunction "SCLIN_P$3") (pintype "bidirectional"))
    )
    (net (code "41") (name "Net-(U5-SDAIN)") (class "Default")
      (node (ref "JMP1") (pin "3") (pinfunction "3_3") (pintype "passive"))
      (node (ref "U5") (pin "P$6") (pinfunction "SDAIN_P$6") (pintype "bidirectional"))
    )
    (net (code "42") (name "Net-(X2A-S)") (class "Default")
      (node (ref "R11") (pin "1") (pinfunction "1_1") (pintype "bidirectional"))
      (node (ref "X2") (pin "1") (pinfunction "S_1") (pintype "passive"))
    )
    (net (code "43") (name "Net-(X2B-S)") (class "Default")
      (node (ref "R12") (pin "1") (pinfunction "1_1") (pintype "bidirectional"))
      (node (ref "X2") (pin "2") (pinfunction "S_2") (pintype "passive"))
    )
    (net (code "44") (name "RTS") (class "Default")
      (node (ref "IC2") (pin "19") (pinfunction "RTS_19") (pintype "bidirectional"))
      (node (ref "U3") (pin "1") (pinfunction "S_1") (pintype "passive"))
      (node (ref "U3") (pin "5") (pinfunction "G_5") (pintype "passive"))
    )
    (net (code "45") (name "RXD") (class "Default")
      (node (ref "R2") (pin "2") (pinfunction "2_2") (pintype "bidirectional"))
      (node (ref "TP4") (pin "TP") (pinfunction "TP_TP") (pintype "input"))
      (node (ref "U1") (pin "34") (pinfunction "RXD0_34") (pintype "bidirectional"))
    )
    (net (code "46") (name "RXLED") (class "Default")
      (node (ref "IC2") (pin "14") (pinfunction "CBUS1_14") (pintype "bidirectional"))
      (node (ref "R3") (pin "1") (pinfunction "1_1") (pintype "bidirectional"))
    )
    (net (code "47") (name "SD0") (class "Default")
      (node (ref "U1") (pin "21") (pinfunction "SD0_21") (pintype "bidirectional"))
    )
    (net (code "48") (name "SD1") (class "Default")
      (node (ref "U1") (pin "22") (pinfunction "SD1_22") (pintype "bidirectional"))
    )
    (net (code "49") (name "SD2") (class "Default")
      (node (ref "R11") (pin "2") (pinfunction "2_2") (pintype "bidirectional"))
      (node (ref "U1") (pin "17") (pinfunction "SD2_17") (pintype "bidirectional"))
    )
    (net (code "50") (name "SD3") (class "Default")
      (node (ref "R12") (pin "2") (pinfunction "2_2") (pintype "bidirectional"))
      (node (ref "U1") (pin "18") (pinfunction "SD3_18") (pintype "bidirectional"))
    )
    (net (code "51") (name "SENSOR_VN") (class "Default")
      (node (ref "U1") (pin "5") (pinfunction "SENSOR_VN_5") (pintype "bidirectional"))
    )
    (net (code "52") (name "SENSOR_VP") (class "Default")
      (node (ref "U1") (pin "4") (pinfunction "SENSOR_VP_4") (pintype "bidirectional"))
    )
    (net (code "53") (name "TXD") (class "Default")
      (node (ref "R5") (pin "2") (pinfunction "2_2") (pintype "bidirectional"))
      (node (ref "TP3") (pin "TP") (pinfunction "TP_TP") (pintype "input"))
      (node (ref "U1") (pin "35") (pinfunction "TXD0_35") (pintype "bidirectional"))
    )
    (net (code "54") (name "TXLED") (class "Default")
      (node (ref "IC2") (pin "7") (pinfunction "CBUS2_7") (pintype "bidirectional"))
      (node (ref "R4") (pin "1") (pinfunction "1_1") (pintype "bidirectional"))
    )
    (net (code "55") (name "USBDM") (class "Default")
      (node (ref "D1") (pin "3") (pinfunction "3_3") (pintype "bidirectional"))
      (node (ref "IC2") (pin "9") (pinfunction "USBDM_9") (pintype "bidirectional"))
      (node (ref "USB1") (pin "2") (pinfunction "D-_2") (pintype "bidirectional"))
    )
    (net (code "56") (name "USBDP") (class "Default")
      (node (ref "D1") (pin "4") (pinfunction "4_4") (pintype "bidirectional"))
      (node (ref "IC2") (pin "8") (pinfunction "USBDP_8") (pintype "bidirectional"))
      (node (ref "USB1") (pin "3") (pinfunction "D+_3") (pintype "bidirectional"))
    )
    (net (code "57") (name "unconnected-(D1-Pad6)") (class "Default")
      (node (ref "D1") (pin "6") (pinfunction "6_6") (pintype "bidirectional"))
    )
    (net (code "58") (name "unconnected-(IC2-CBUS0-Pad15)") (class "Default")
      (node (ref "IC2") (pin "15") (pinfunction "CBUS0_15") (pintype "bidirectional"))
    )
    (net (code "59") (name "unconnected-(IC2-CBUS3-Pad16)") (class "Default")
      (node (ref "IC2") (pin "16") (pinfunction "CBUS3_16") (pintype "bidirectional"))
    )
    (net (code "60") (name "unconnected-(IC2-CTS-Pad6)") (class "Default")
      (node (ref "IC2") (pin "6") (pinfunction "CTS_6") (pintype "bidirectional"))
    )
    (net (code "61") (name "unconnected-(IC2-DCD-Pad5)") (class "Default")
      (node (ref "IC2") (pin "5") (pinfunction "DCD_5") (pintype "bidirectional"))
    )
    (net (code "62") (name "unconnected-(IC2-DSR-Pad4)") (class "Default")
      (node (ref "IC2") (pin "4") (pinfunction "DSR_4") (pintype "bidirectional"))
    )
    (net (code "63") (name "unconnected-(IC2-RI-Pad2)") (class "Default")
      (node (ref "IC2") (pin "2") (pinfunction "RI_2") (pintype "bidirectional"))
    )
    (net (code "64") (name "unconnected-(U1-NC-Pad32)") (class "Default")
      (node (ref "U1") (pin "32") (pinfunction "NC_32") (pintype "bidirectional"))
    )
    (net (code "65") (name "unconnected-(U1-NC1-Pad27)") (class "Default")
      (node (ref "U1") (pin "27") (pinfunction "NC1_27") (pintype "bidirectional"))
    )
    (net (code "66") (name "unconnected-(U1-NC2-Pad28)") (class "Default")
      (node (ref "U1") (pin "28") (pinfunction "NC2_28") (pintype "bidirectional"))
    )
    (net (code "67") (name "unconnected-(U2-OC-Pad3)") (class "Default")
      (node (ref "U2") (pin "3") (pinfunction "OC_3") (pintype "bidirectional"))
    )
  )
)
